# P16-Connector.net
KiCad netlist of a schematic drawn in Altium Designer
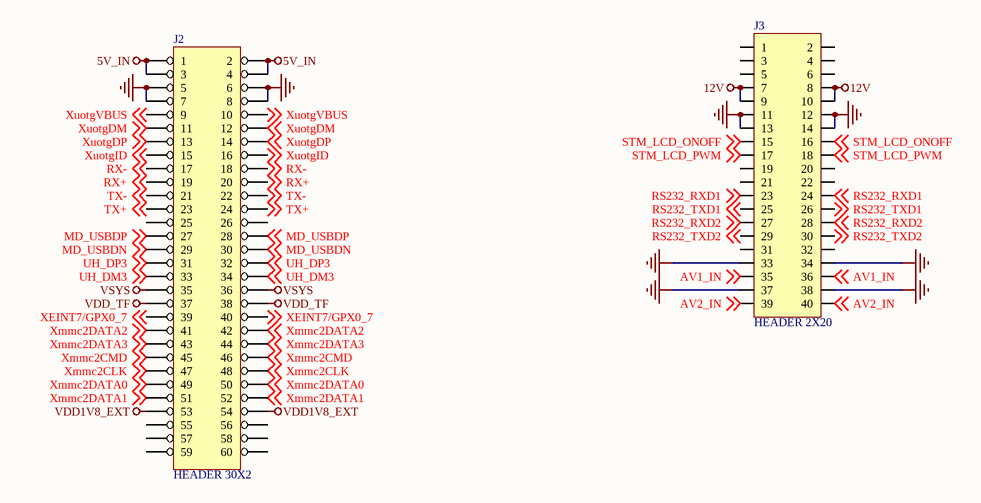
[diagram p0: P16-Connector.SchDoc]

(export (version "E")
  (design (tool "Eeschema 10.0.6"))
  (components
    (comp (ref "J2")
      (value "HEADER 30X2")
      (footprint "HD2X30-2.00")
      (libsource (lib "Connector Class") (part "HEADER 30X2"))
    )
    (comp (ref "J3")
      (value "HEADER 2X20")
      (footprint "HD2X20-2.00")
      (libsource (lib "Connector Class") (part "HEADER 2X20"))
    )
  )
  (nets
    (net (code "1") (name "5V_IN") (class "Default")
      (node (ref "J2") (pin "1") (pinfunction "1_1") (pintype "passive"))
      (node (ref "J2") (pin "2") (pinfunction "2_2") (pintype "passive"))
      (node (ref "J2") (pin "3") (pinfunction "3_3") (pintype "passive"))
      (node (ref "J2") (pin "4") (pinfunction "4_4") (pintype "passive"))
    )
    (net (code "2") (name "12V") (class "Default")
      (node (ref "J3") (pin "10") (pinfunction "10_10") (pintype "passive"))
      (node (ref "J3") (pin "7") (pinfunction "7_7") (pintype "passive"))
      (node (ref "J3") (pin "8") (pinfunction "8_8") (pintype "passive"))
      (node (ref "J3") (pin "9") (pinfunction "9_9") (pintype "passive"))
    )
    (net (code "3") (name "AV1_IN") (class "Default")
      (node (ref "J3") (pin "35") (pinfunction "35_35") (pintype "passive"))
      (node (ref "J3") (pin "36") (pinfunction "36_36") (pintype "passive"))
    )
    (net (code "4") (name "AV2_IN") (class "Default")
      (node (ref "J3") (pin "39") (pinfunction "39_39") (pintype "passive"))
      (node (ref "J3") (pin "40") (pinfunction "40_40") (pintype "passive"))
    )
    (net (code "5") (name "GND") (class "Default")
      (node (ref "J2") (pin "5") (pinfunction "5_5") (pintype "passive"))
      (node (ref "J2") (pin "6") (pinfunction "6_6") (pintype "passive"))
      (node (ref "J2") (pin "7") (pinfunction "7_7") (pintype "passive"))
      (node (ref "J2") (pin "8") (pinfunction "8_8") (pintype "passive"))
      (node (ref "J3") (pin "11") (pinfunction "11_11") (pintype "passive"))
      (node (ref "J3") (pin "12") (pinfunction "12_12") (pintype "passive"))
      (node (ref "J3") (pin "13") (pinfunction "13_13") (pintype "passive"))
      (node (ref "J3") (pin "14") (pinfunction "14_14") (pintype "passive"))
      (node (ref "J3") (pin "33") (pinfunction "33_33") (pintype "passive"))
      (node (ref "J3") (pin "34") (pinfunction "34_34") (pintype "passive"))
      (node (ref "J3") (pin "37") (pinfunction "37_37") (pintype "passive"))
      (node (ref "J3") (pin "38") (pinfunction "38_38") (pintype "passive"))
    )
    (net (code "6") (name "MD_USBDN") (class "Default")
      (node (ref "J2") (pin "29") (pinfunction "29_29") (pintype "passive"))
      (node (ref "J2") (pin "30") (pinfunction "30_30") (pintype "passive"))
    )
    (net (code "7") (name "MD_USBDP") (class "Default")
      (node (ref "J2") (pin "27") (pinfunction "27_27") (pintype "passive"))
      (node (ref "J2") (pin "28") (pinfunction "28_28") (pintype "passive"))
    )
    (net (code "8") (name "RS232_RXD1") (class "Default")
      (node (ref "J3") (pin "23") (pinfunction "23_23") (pintype "passive"))
      (node (ref "J3") (pin "24") (pinfunction "24_24") (pintype "passive"))
    )
    (net (code "9") (name "RS232_RXD2") (class "Default")
      (node (ref "J3") (pin "27") (pinfunction "27_27") (pintype "passive"))
      (node (ref "J3") (pin "28") (pinfunction "28_28") (pintype "passive"))
    )
    (net (code "10") (name "RS232_TXD1") (class "Default")
      (node (ref "J3") (pin "25") (pinfunction "25_25") (pintype "passive"))
      (node (ref "J3") (pin "26") (pinfunction "26_26") (pintype "passive"))
    )
    (net (code "11") (name "RS232_TXD2") (class "Default")
      (node (ref "J3") (pin "29") (pinfunction "29_29") (pintype "passive"))
      (node (ref "J3") (pin "30") (pinfunction "30_30") (pintype "passive"))
    )
    (net (code "12") (name "RX+") (class "Default")
      (node (ref "J2") (pin "19") (pinfunction "19_19") (pintype "passive"))
      (node (ref "J2") (pin "20") (pinfunction "20_20") (pintype "passive"))
    )
    (net (code "13") (name "RX-") (class "Default")
      (node (ref "J2") (pin "17") (pinfunction "17_17") (pintype "passive"))
      (node (ref "J2") (pin "18") (pinfunction "18_18") (pintype "passive"))
    )
    (net (code "14") (name "STM_LCD_ONOFF") (class "Default")
      (node (ref "J3") (pin "15") (pinfunction "15_15") (pintype "passive"))
      (node (ref "J3") (pin "16") (pinfunction "16_16") (pintype "passive"))
    )
    (net (code "15") (name "STM_LCD_PWM") (class "Default")
      (node (ref "J3") (pin "17") (pinfunction "17_17") (pintype "passive"))
      (node (ref "J3") (pin "18") (pinfunction "18_18") (pintype "passive"))
    )
    (net (code "16") (name "TX+") (class "Default")
      (node (ref "J2") (pin "23") (pinfunction "23_23") (pintype "passive"))
      (node (ref "J2") (pin "24") (pinfunction "24_24") (pintype "passive"))
    )
    (net (code "17") (name "TX-") (class "Default")
      (node (ref "J2") (pin "21") (pinfunction "21_21") (pintype "passive"))
      (node (ref "J2") (pin "22") (pinfunction "22_22") (pintype "passive"))
    )
    (net (code "18") (name "UH_DM3") (class "Default")
      (node (ref "J2") (pin "33") (pinfunction "33_33") (pintype "passive"))
      (node (ref "J2") (pin "34") (pinfunction "34_34") (pintype "passive"))
    )
    (net (code "19") (name "UH_DP3") (class "Default")
      (node (ref "J2") (pin "31") (pinfunction "31_31") (pintype "passive"))
      (node (ref "J2") (pin "32") (pinfunction "32_32") (pintype "passive"))
    )
    (net (code "20") (name "VDD1V8_EXT") (class "Default")
      (node (ref "J2") (pin "53") (pinfunction "53_53") (pintype "passive"))
      (node (ref "J2") (pin "54") (pinfunction "54_54") (pintype "passive"))
    )
    (net (code "21") (name "VDD_TF") (class "Default")
      (node (ref "J2") (pin "37") (pinfunction "37_37") (pintype "passive"))
      (node (ref "J2") (pin "38") (pinfunction "38_38") (pintype "passive"))
    )
    (net (code "22") (name "VSYS") (class "Default")
      (node (ref "J2") (pin "35") (pinfunction "35_35") (pintype "passive"))
      (node (ref "J2") (pin "36") (pinfunction "36_36") (pintype "passive"))
    )
    (net (code "23") (name "XEINT7{slash}GPX0_7") (class "Default")
      (node (ref "J2") (pin "39") (pinfunction "39_39") (pintype "passive"))
      (node (ref "J2") (pin "40") (pinfunction "40_40") (pintype "passive"))
    )
    (net (code "24") (name "Xmmc2CLK") (class "Default")
      (node (ref "J2") (pin "47") (pinfunction "47_47") (pintype "passive"))
      (node (ref "J2") (pin "48") (pinfunction "48_48") (pintype "passive"))
    )
    (net (code "25") (name "Xmmc2CMD") (class "Default")
      (node (ref "J2") (pin "45") (pinfunction "45_45") (pintype "passive"))
      (node (ref "J2") (pin "46") (pinfunction "46_46") (pintype "passive"))
    )
    (net (code "26") (name "Xmmc2DATA0") (class "Default")
      (node (ref "J2") (pin "49") (pinfunction "49_49") (pintype "passive"))
      (node (ref "J2") (pin "50") (pinfunction "50_50") (pintype "passive"))
    )
    (net (code "27") (name "Xmmc2DATA1") (class "Default")
      (node (ref "J2") (pin "51") (pinfunction "51_51") (pintype "passive"))
      (node (ref "J2") (pin "52") (pinfunction "52_52") (pintype "passive"))
    )
    (net (code "28") (name "Xmmc2DATA2") (class "Default")
      (node (ref "J2") (pin "41") (pinfunction "41_41") (pintype "passive"))
      (node (ref "J2") (pin "42") (pinfunction "42_42") (pintype "passive"))
    )
    (net (code "29") (name "Xmmc2DATA3") (class "Default")
      (node (ref "J2") (pin "43") (pinfunction "43_43") (pintype "passive"))
      (node (ref "J2") (pin "44") (pinfunction "44_44") (pintype "passive"))
    )
    (net (code "30") (name "XuotgDM") (class "Default")
      (node (ref "J2") (pin "11") (pinfunction "11_11") (pintype "passive"))
      (node (ref "J2") (pin "12") (pinfunction "12_12") (pintype "passive"))
    )
    (net (code "31") (name "XuotgDP") (class "Default")
      (node (ref "J2") (pin "13") (pinfunction "13_13") (pintype "passive"))
      (node (ref "J2") (pin "14") (pinfunction "14_14") (pintype "passive"))
    )
    (net (code "32") (name "XuotgID") (class "Default")
      (node (ref "J2") (pin "15") (pinfunction "15_15") (pintype "passive"))
      (node (ref "J2") (pin "16") (pinfunction "16_16") (pintype "passive"))
    )
    (net (code "33") (name "XuotgVBUS") (class "Default")
      (node (ref "J2") (pin "10") (pinfunction "10_10") (pintype "passive"))
      (node (ref "J2") (pin "9") (pinfunction "9_9") (pintype "passive"))
    )
    (net (code "34") (name "unconnected-(J2-Pad25)") (class "Default")
      (node (ref "J2") (pin "25") (pinfunction "25_25") (pintype "passive"))
    )
    (net (code "35") (name "unconnected-(J2-Pad26)") (class "Default")
      (node (ref "J2") (pin "26") (pinfunction "26_26") (pintype "passive"))
    )
    (net (code "36") (name "unconnected-(J2-Pad55)") (class "Default")
      (node (ref "J2") (pin "55") (pinfunction "55_55") (pintype "passive"))
    )
    (net (code "37") (name "unconnected-(J2-Pad56)") (class "Default")
      (node (ref "J2") (pin "56") (pinfunction "56_56") (pintype "passive"))
    )
    (net (code "38") (name "unconnected-(J2-Pad57)") (class "Default")
      (node (ref "J2") (pin "57") (pinfunction "57_57") (pintype "passive"))
    )
    (net (code "39") (name "unconnected-(J2-Pad58)") (class "Default")
      (node (ref "J2") (pin "58") (pinfunction "58_58") (pintype "passive"))
    )
    (net (code "40") (name "unconnected-(J2-Pad59)") (class "Default")
      (node (ref "J2") (pin "59") (pinfunction "59_59") (pintype "passive"))
    )
    (net (code "41") (name "unconnected-(J2-Pad60)") (class "Default")
      (node (ref "J2") (pin "60") (pinfunction "60_60") (pintype "passive"))
    )
    (net (code "42") (name "unconnected-(J3-Pad1)") (class "Default")
      (node (ref "J3") (pin "1") (pinfunction "1_1") (pintype "passive"))
    )
    (net (code "43") (name "unconnected-(J3-Pad2)") (class "Default")
      (node (ref "J3") (pin "2") (pinfunction "2_2") (pintype "passive"))
    )
    (net (code "44") (name "unconnected-(J3-Pad3)") (class "Default")
      (node (ref "J3") (pin "3") (pinfunction "3_3") (pintype "passive"))
    )
    (net (code "45") (name "unconnected-(J3-Pad4)") (class "Default")
      (node (ref "J3") (pin "4") (pinfunction "4_4") (pintype "passive"))
    )
    (net (code "46") (name "unconnected-(J3-Pad5)") (class "Default")
      (node (ref "J3") (pin "5") (pinfunction "5_5") (pintype "passive"))
    )
    (net (code "47") (name "unconnected-(J3-Pad6)") (class "Default")
      (node (ref "J3") (pin "6") (pinfunction "6_6") (pintype "passive"))
    )
    (net (code "48") (name "unconnected-(J3-Pad19)") (class "Default")
      (node (ref "J3") (pin "19") (pinfunction "19_19") (pintype "passive"))
    )
    (net (code "49") (name "unconnected-(J3-Pad20)") (class "Default")
      (node (ref "J3") (pin "20") (pinfunction "20_20") (pintype "passive"))
    )
    (net (code "50") (name "unconnected-(J3-Pad21)") (class "Default")
      (node (ref "J3") (pin "21") (pinfunction "21_21") (pintype "passive"))
    )
    (net (code "51") (name "unconnected-(J3-Pad22)") (class "Default")
      (node (ref "J3") (pin "22") (pinfunction "22_22") (pintype "passive"))
    )
    (net (code "52") (name "unconnected-(J3-Pad31)") (class "Default")
      (node (ref "J3") (pin "31") (pinfunction "31_31") (pintype "passive"))
    )
    (net (code "53") (name "unconnected-(J3-Pad32)") (class "Default")
      (node (ref "J3") (pin "32") (pinfunction "32_32") (pintype "passive"))
    )
  )
)
